# Sheet3.net
KiCad netlist of a schematic drawn in Altium Designer
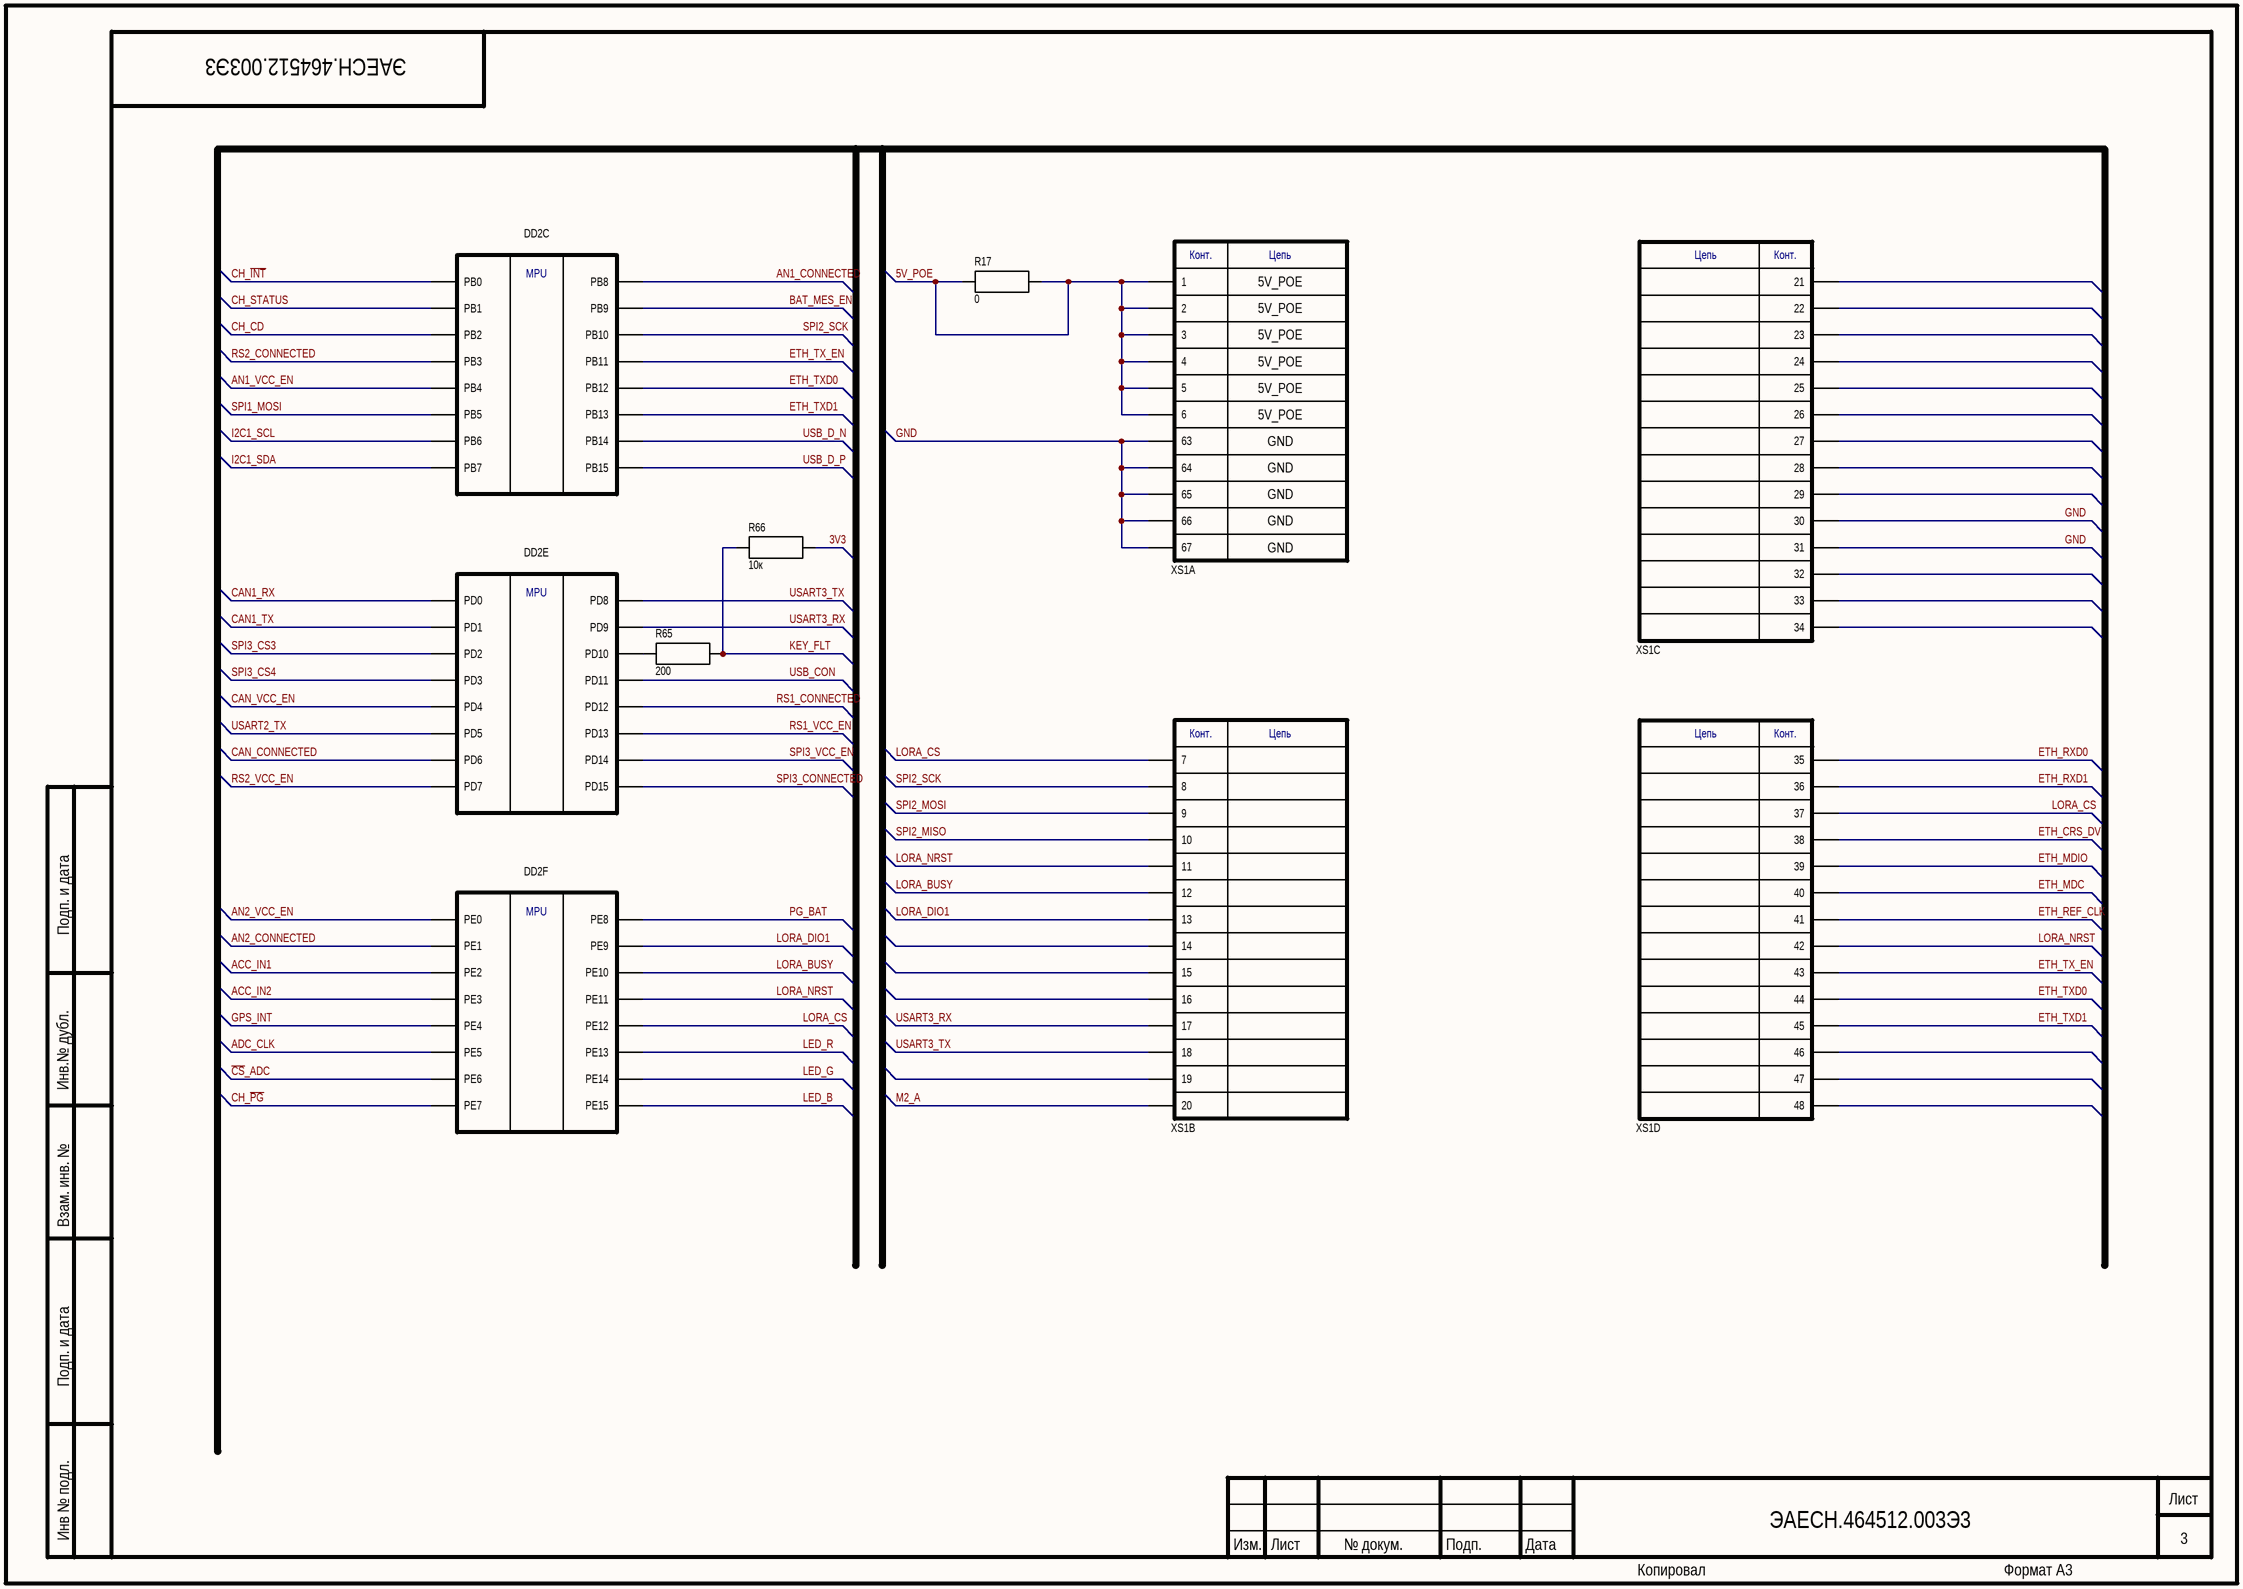
[diagram p0: Sheet3.SchDoc]

(export (version "E")
  (design (tool "Eeschema 10.0.6"))
  (components
    (comp (ref "DD2")
      (value "STM32F207VCTx")
      (footprint "LQFP100")
      (libsource (lib "Schlib1") (part "STM32F207VCTx"))
    )
    (comp (ref "R17")
      (value "0")
      (footprint "R1206")
      (fields (field (name "Comment") "R"))
      (libsource (lib "Schlib1") (part "R"))
    )
    (comp (ref "R65")
      (value "200")
      (footprint "R0603")
      (fields (field (name "Comment") "R"))
      (libsource (lib "Schlib1") (part "R"))
    )
    (comp (ref "R66")
      (value "10к")
      (footprint "R0603")
      (fields (field (name "Comment") "R"))
      (libsource (lib "Schlib1") (part "R"))
    )
    (comp (ref "XS1") (value "M.2") (footprint "M.2") (libsource (lib "Schlib1") (part "M.2")))
  )
  (nets
    (net (code "1") (name "/3V3") (class "Default")
      (node (ref "R66") (pin "2") (pinfunction "2_2") (pintype "passive"))
    )
    (net (code "2") (name "/5V_POE") (class "Default")
      (node (ref "R17") (pin "1") (pinfunction "1_1") (pintype "passive"))
      (node (ref "R17") (pin "2") (pinfunction "2_2") (pintype "passive"))
      (node (ref "XS1") (pin "1") (pinfunction "1_1") (pintype "passive"))
      (node (ref "XS1") (pin "2") (pinfunction "2_2") (pintype "passive"))
      (node (ref "XS1") (pin "3") (pinfunction "3_3") (pintype "passive"))
      (node (ref "XS1") (pin "4") (pinfunction "4_4") (pintype "passive"))
      (node (ref "XS1") (pin "5") (pinfunction "5_5") (pintype "passive"))
      (node (ref "XS1") (pin "6") (pinfunction "6_6") (pintype "passive"))
    )
    (net (code "3") (name "/ACC_IN1") (class "Default")
      (node (ref "DD2") (pin "1") (pinfunction "PE2_1") (pintype "passive"))
    )
    (net (code "4") (name "/ACC_IN2") (class "Default")
      (node (ref "DD2") (pin "2") (pinfunction "PE3_2") (pintype "passive"))
    )
    (net (code "5") (name "/ADC_CLK") (class "Default")
      (node (ref "DD2") (pin "4") (pinfunction "PE5_4") (pintype "passive"))
    )
    (net (code "6") (name "/AN1_CONNECTED") (class "Default")
      (node (ref "DD2") (pin "95") (pinfunction "PB8_95") (pintype "passive"))
    )
    (net (code "7") (name "/AN1_VCC_EN") (class "Default")
      (node (ref "DD2") (pin "90") (pinfunction "PB4_90") (pintype "passive"))
    )
    (net (code "8") (name "/AN2_CONNECTED") (class "Default")
      (node (ref "DD2") (pin "98") (pinfunction "PE1_98") (pintype "passive"))
    )
    (net (code "9") (name "/AN2_VCC_EN") (class "Default")
      (node (ref "DD2") (pin "97") (pinfunction "PE0_97") (pintype "passive"))
    )
    (net (code "10") (name "/BAT_MES_EN") (class "Default")
      (node (ref "DD2") (pin "96") (pinfunction "PB9_96") (pintype "passive"))
    )
    (net (code "11") (name "/CAN1_RX") (class "Default")
      (node (ref "DD2") (pin "81") (pinfunction "PD0_81") (pintype "passive"))
    )
    (net (code "12") (name "/CAN1_TX") (class "Default")
      (node (ref "DD2") (pin "82") (pinfunction "PD1_82") (pintype "passive"))
    )
    (net (code "13") (name "/CAN_CONNECTED") (class "Default")
      (node (ref "DD2") (pin "87") (pinfunction "PD6_87") (pintype "passive"))
    )
    (net (code "14") (name "/CAN_VCC_EN") (class "Default")
      (node (ref "DD2") (pin "85") (pinfunction "PD4_85") (pintype "passive"))
    )
    (net (code "15") (name "/CH_CD") (class "Default")
      (node (ref "DD2") (pin "37") (pinfunction "PB2_37") (pintype "passive"))
    )
    (net (code "16") (name "/CH_STATUS") (class "Default")
      (node (ref "DD2") (pin "36") (pinfunction "PB1_36") (pintype "passive"))
    )
    (net (code "17") (name "/CH_~{INT}") (class "Default")
      (node (ref "DD2") (pin "35") (pinfunction "PB0_35") (pintype "passive"))
    )
    (net (code "18") (name "/CH_~{PG}") (class "Default")
      (node (ref "DD2") (pin "38") (pinfunction "PE7_38") (pintype "passive"))
    )
    (net (code "19") (name "/ETH_CRS_DV") (class "Default")
      (node (ref "XS1") (pin "38") (pinfunction "38_38") (pintype "passive"))
    )
    (net (code "20") (name "/ETH_MDC") (class "Default")
      (node (ref "XS1") (pin "40") (pinfunction "40_40") (pintype "passive"))
    )
    (net (code "21") (name "/ETH_MDIO") (class "Default")
      (node (ref "XS1") (pin "39") (pinfunction "39_39") (pintype "passive"))
    )
    (net (code "22") (name "/ETH_REF_CLK") (class "Default")
      (node (ref "XS1") (pin "41") (pinfunction "41_41") (pintype "passive"))
    )
    (net (code "23") (name "/ETH_RXD0") (class "Default")
      (node (ref "XS1") (pin "35") (pinfunction "35_35") (pintype "passive"))
    )
    (net (code "24") (name "/ETH_RXD1") (class "Default")
      (node (ref "XS1") (pin "36") (pinfunction "36_36") (pintype "passive"))
    )
    (net (code "25") (name "/ETH_TXD0") (class "Default")
      (node (ref "DD2") (pin "51") (pinfunction "PB12_51") (pintype "passive"))
      (node (ref "XS1") (pin "44") (pinfunction "44_44") (pintype "passive"))
    )
    (net (code "26") (name "/ETH_TXD1") (class "Default")
      (node (ref "DD2") (pin "52") (pinfunction "PB13_52") (pintype "passive"))
      (node (ref "XS1") (pin "45") (pinfunction "45_45") (pintype "passive"))
    )
    (net (code "27") (name "/ETH_TX_EN") (class "Default")
      (node (ref "DD2") (pin "48") (pinfunction "PB11_48") (pintype "passive"))
      (node (ref "XS1") (pin "43") (pinfunction "43_43") (pintype "passive"))
    )
    (net (code "28") (name "/GND") (class "Default")
      (node (ref "XS1") (pin "30") (pinfunction "30_30") (pintype "passive"))
      (node (ref "XS1") (pin "31") (pinfunction "31_31") (pintype "passive"))
      (node (ref "XS1") (pin "63") (pinfunction "63_63") (pintype "passive"))
      (node (ref "XS1") (pin "64") (pinfunction "64_64") (pintype "passive"))
      (node (ref "XS1") (pin "65") (pinfunction "65_65") (pintype "passive"))
      (node (ref "XS1") (pin "66") (pinfunction "66_66") (pintype "passive"))
      (node (ref "XS1") (pin "67") (pinfunction "67_67") (pintype "passive"))
    )
    (net (code "29") (name "/GPS_INT") (class "Default")
      (node (ref "DD2") (pin "3") (pinfunction "PE4_3") (pintype "passive"))
    )
    (net (code "30") (name "/I2C1_SCL") (class "Default")
      (node (ref "DD2") (pin "92") (pinfunction "PB6_92") (pintype "passive"))
    )
    (net (code "31") (name "/I2C1_SDA") (class "Default")
      (node (ref "DD2") (pin "93") (pinfunction "PB7_93") (pintype "passive"))
    )
    (net (code "32") (name "/KEY_FLT") (class "Default")
      (node (ref "R65") (pin "2") (pinfunction "2_2") (pintype "passive"))
      (node (ref "R66") (pin "1") (pinfunction "1_1") (pintype "passive"))
    )
    (net (code "33") (name "/LED_B") (class "Default")
      (node (ref "DD2") (pin "46") (pinfunction "PE15_46") (pintype "passive"))
    )
    (net (code "34") (name "/LED_G") (class "Default")
      (node (ref "DD2") (pin "45") (pinfunction "PE14_45") (pintype "passive"))
    )
    (net (code "35") (name "/LED_R") (class "Default")
      (node (ref "DD2") (pin "44") (pinfunction "PE13_44") (pintype "passive"))
    )
    (net (code "36") (name "/LORA_BUSY") (class "Default")
      (node (ref "DD2") (pin "41") (pinfunction "PE10_41") (pintype "passive"))
      (node (ref "XS1") (pin "12") (pinfunction "12_12") (pintype "passive"))
    )
    (net (code "37") (name "/LORA_CS") (class "Default")
      (node (ref "DD2") (pin "43") (pinfunction "PE12_43") (pintype "passive"))
      (node (ref "XS1") (pin "37") (pinfunction "37_37") (pintype "passive"))
      (node (ref "XS1") (pin "7") (pinfunction "7_7") (pintype "passive"))
    )
    (net (code "38") (name "/LORA_DIO1") (class "Default")
      (node (ref "DD2") (pin "40") (pinfunction "PE9_40") (pintype "passive"))
      (node (ref "XS1") (pin "13") (pinfunction "13_13") (pintype "passive"))
    )
    (net (code "39") (name "/LORA_NRST") (class "Default")
      (node (ref "DD2") (pin "42") (pinfunction "PE11_42") (pintype "passive"))
      (node (ref "XS1") (pin "11") (pinfunction "11_11") (pintype "passive"))
      (node (ref "XS1") (pin "42") (pinfunction "42_42") (pintype "passive"))
    )
    (net (code "40") (name "/M2_A") (class "Default")
      (node (ref "XS1") (pin "20") (pinfunction "20_20") (pintype "passive"))
    )
    (net (code "41") (name "/PG_BAT") (class "Default")
      (node (ref "DD2") (pin "39") (pinfunction "PE8_39") (pintype "passive"))
    )
    (net (code "42") (name "/RS1_CONNECTED") (class "Default")
      (node (ref "DD2") (pin "59") (pinfunction "PD12_59") (pintype "passive"))
    )
    (net (code "43") (name "/RS1_VCC_EN") (class "Default")
      (node (ref "DD2") (pin "60") (pinfunction "PD13_60") (pintype "passive"))
    )
    (net (code "44") (name "/RS2_CONNECTED") (class "Default")
      (node (ref "DD2") (pin "89") (pinfunction "PB3_89") (pintype "passive"))
    )
    (net (code "45") (name "/RS2_VCC_EN") (class "Default")
      (node (ref "DD2") (pin "88") (pinfunction "PD7_88") (pintype "passive"))
    )
    (net (code "46") (name "/SPI1_MOSI") (class "Default")
      (node (ref "DD2") (pin "91") (pinfunction "PB5_91") (pintype "passive"))
    )
    (net (code "47") (name "/SPI2_MISO") (class "Default")
      (node (ref "XS1") (pin "10") (pinfunction "10_10") (pintype "passive"))
    )
    (net (code "48") (name "/SPI2_MOSI") (class "Default")
      (node (ref "XS1") (pin "9") (pinfunction "9_9") (pintype "passive"))
    )
    (net (code "49") (name "/SPI2_SCK") (class "Default")
      (node (ref "DD2") (pin "47") (pinfunction "PB10_47") (pintype "passive"))
      (node (ref "XS1") (pin "8") (pinfunction "8_8") (pintype "passive"))
    )
    (net (code "50") (name "/SPI3_CONNECTED") (class "Default")
      (node (ref "DD2") (pin "62") (pinfunction "PD15_62") (pintype "passive"))
    )
    (net (code "51") (name "/SPI3_CS3") (class "Default")
      (node (ref "DD2") (pin "83") (pinfunction "PD2_83") (pintype "passive"))
    )
    (net (code "52") (name "/SPI3_CS4") (class "Default")
      (node (ref "DD2") (pin "84") (pinfunction "PD3_84") (pintype "passive"))
    )
    (net (code "53") (name "/SPI3_VCC_EN") (class "Default")
      (node (ref "DD2") (pin "61") (pinfunction "PD14_61") (pintype "passive"))
    )
    (net (code "54") (name "/USART2_TX") (class "Default")
      (node (ref "DD2") (pin "86") (pinfunction "PD5_86") (pintype "passive"))
    )
    (net (code "55") (name "/USART3_RX") (class "Default")
      (node (ref "DD2") (pin "56") (pinfunction "PD9_56") (pintype "passive"))
      (node (ref "XS1") (pin "17") (pinfunction "17_17") (pintype "passive"))
    )
    (net (code "56") (name "/USART3_TX") (class "Default")
      (node (ref "DD2") (pin "55") (pinfunction "PD8_55") (pintype "passive"))
      (node (ref "XS1") (pin "18") (pinfunction "18_18") (pintype "passive"))
    )
    (net (code "57") (name "/USB_CON") (class "Default")
      (node (ref "DD2") (pin "58") (pinfunction "PD11_58") (pintype "passive"))
    )
    (net (code "58") (name "/USB_D_N") (class "Default")
      (node (ref "DD2") (pin "53") (pinfunction "PB14_53") (pintype "passive"))
    )
    (net (code "59") (name "/USB_D_P") (class "Default")
      (node (ref "DD2") (pin "54") (pinfunction "PB15_54") (pintype "passive"))
    )
    (net (code "60") (name "/~{CS}_ADC") (class "Default")
      (node (ref "DD2") (pin "5") (pinfunction "PE6_5") (pintype "passive"))
    )
    (net (code "61") (name "Net-(DD2E-PD10)") (class "Default")
      (node (ref "DD2") (pin "57") (pinfunction "PD10_57") (pintype "passive"))
      (node (ref "R65") (pin "1") (pinfunction "1_1") (pintype "passive"))
    )
    (net (code "62") (name "unconnected-(XS1-Pad14)") (class "Default")
      (node (ref "XS1") (pin "14") (pinfunction "14_14") (pintype "passive"))
    )
    (net (code "63") (name "unconnected-(XS1-Pad15)") (class "Default")
      (node (ref "XS1") (pin "15") (pinfunction "15_15") (pintype "passive"))
    )
    (net (code "64") (name "unconnected-(XS1-Pad16)") (class "Default")
      (node (ref "XS1") (pin "16") (pinfunction "16_16") (pintype "passive"))
    )
    (net (code "65") (name "unconnected-(XS1-Pad19)") (class "Default")
      (node (ref "XS1") (pin "19") (pinfunction "19_19") (pintype "passive"))
    )
    (net (code "66") (name "unconnected-(XS1-Pad21)") (class "Default")
      (node (ref "XS1") (pin "21") (pinfunction "21_21") (pintype "passive"))
    )
    (net (code "67") (name "unconnected-(XS1-Pad22)") (class "Default")
      (node (ref "XS1") (pin "22") (pinfunction "22_22") (pintype "passive"))
    )
    (net (code "68") (name "unconnected-(XS1-Pad23)") (class "Default")
      (node (ref "XS1") (pin "23") (pinfunction "23_23") (pintype "passive"))
    )
    (net (code "69") (name "unconnected-(XS1-Pad24)") (class "Default")
      (node (ref "XS1") (pin "24") (pinfunction "24_24") (pintype "passive"))
    )
    (net (code "70") (name "unconnected-(XS1-Pad25)") (class "Default")
      (node (ref "XS1") (pin "25") (pinfunction "25_25") (pintype "passive"))
    )
    (net (code "71") (name "unconnected-(XS1-Pad26)") (class "Default")
      (node (ref "XS1") (pin "26") (pinfunction "26_26") (pintype "passive"))
    )
    (net (code "72") (name "unconnected-(XS1-Pad27)") (class "Default")
      (node (ref "XS1") (pin "27") (pinfunction "27_27") (pintype "passive"))
    )
    (net (code "73") (name "unconnected-(XS1-Pad28)") (class "Default")
      (node (ref "XS1") (pin "28") (pinfunction "28_28") (pintype "passive"))
    )
    (net (code "74") (name "unconnected-(XS1-Pad29)") (class "Default")
      (node (ref "XS1") (pin "29") (pinfunction "29_29") (pintype "passive"))
    )
    (net (code "75") (name "unconnected-(XS1-Pad32)") (class "Default")
      (node (ref "XS1") (pin "32") (pinfunction "32_32") (pintype "passive"))
    )
    (net (code "76") (name "unconnected-(XS1-Pad33)") (class "Default")
      (node (ref "XS1") (pin "33") (pinfunction "33_33") (pintype "passive"))
    )
    (net (code "77") (name "unconnected-(XS1-Pad34)") (class "Default")
      (node (ref "XS1") (pin "34") (pinfunction "34_34") (pintype "passive"))
    )
    (net (code "78") (name "unconnected-(XS1-Pad46)") (class "Default")
      (node (ref "XS1") (pin "46") (pinfunction "46_46") (pintype "passive"))
    )
    (net (code "79") (name "unconnected-(XS1-Pad47)") (class "Default")
      (node (ref "XS1") (pin "47") (pinfunction "47_47") (pintype "passive"))
    )
    (net (code "80") (name "unconnected-(XS1-Pad48)") (class "Default")
      (node (ref "XS1") (pin "48") (pinfunction "48_48") (pintype "passive"))
    )
  )
)
